# trehacklab_doorbell.net
KiCad netlist of a schematic drawn in EAGLE
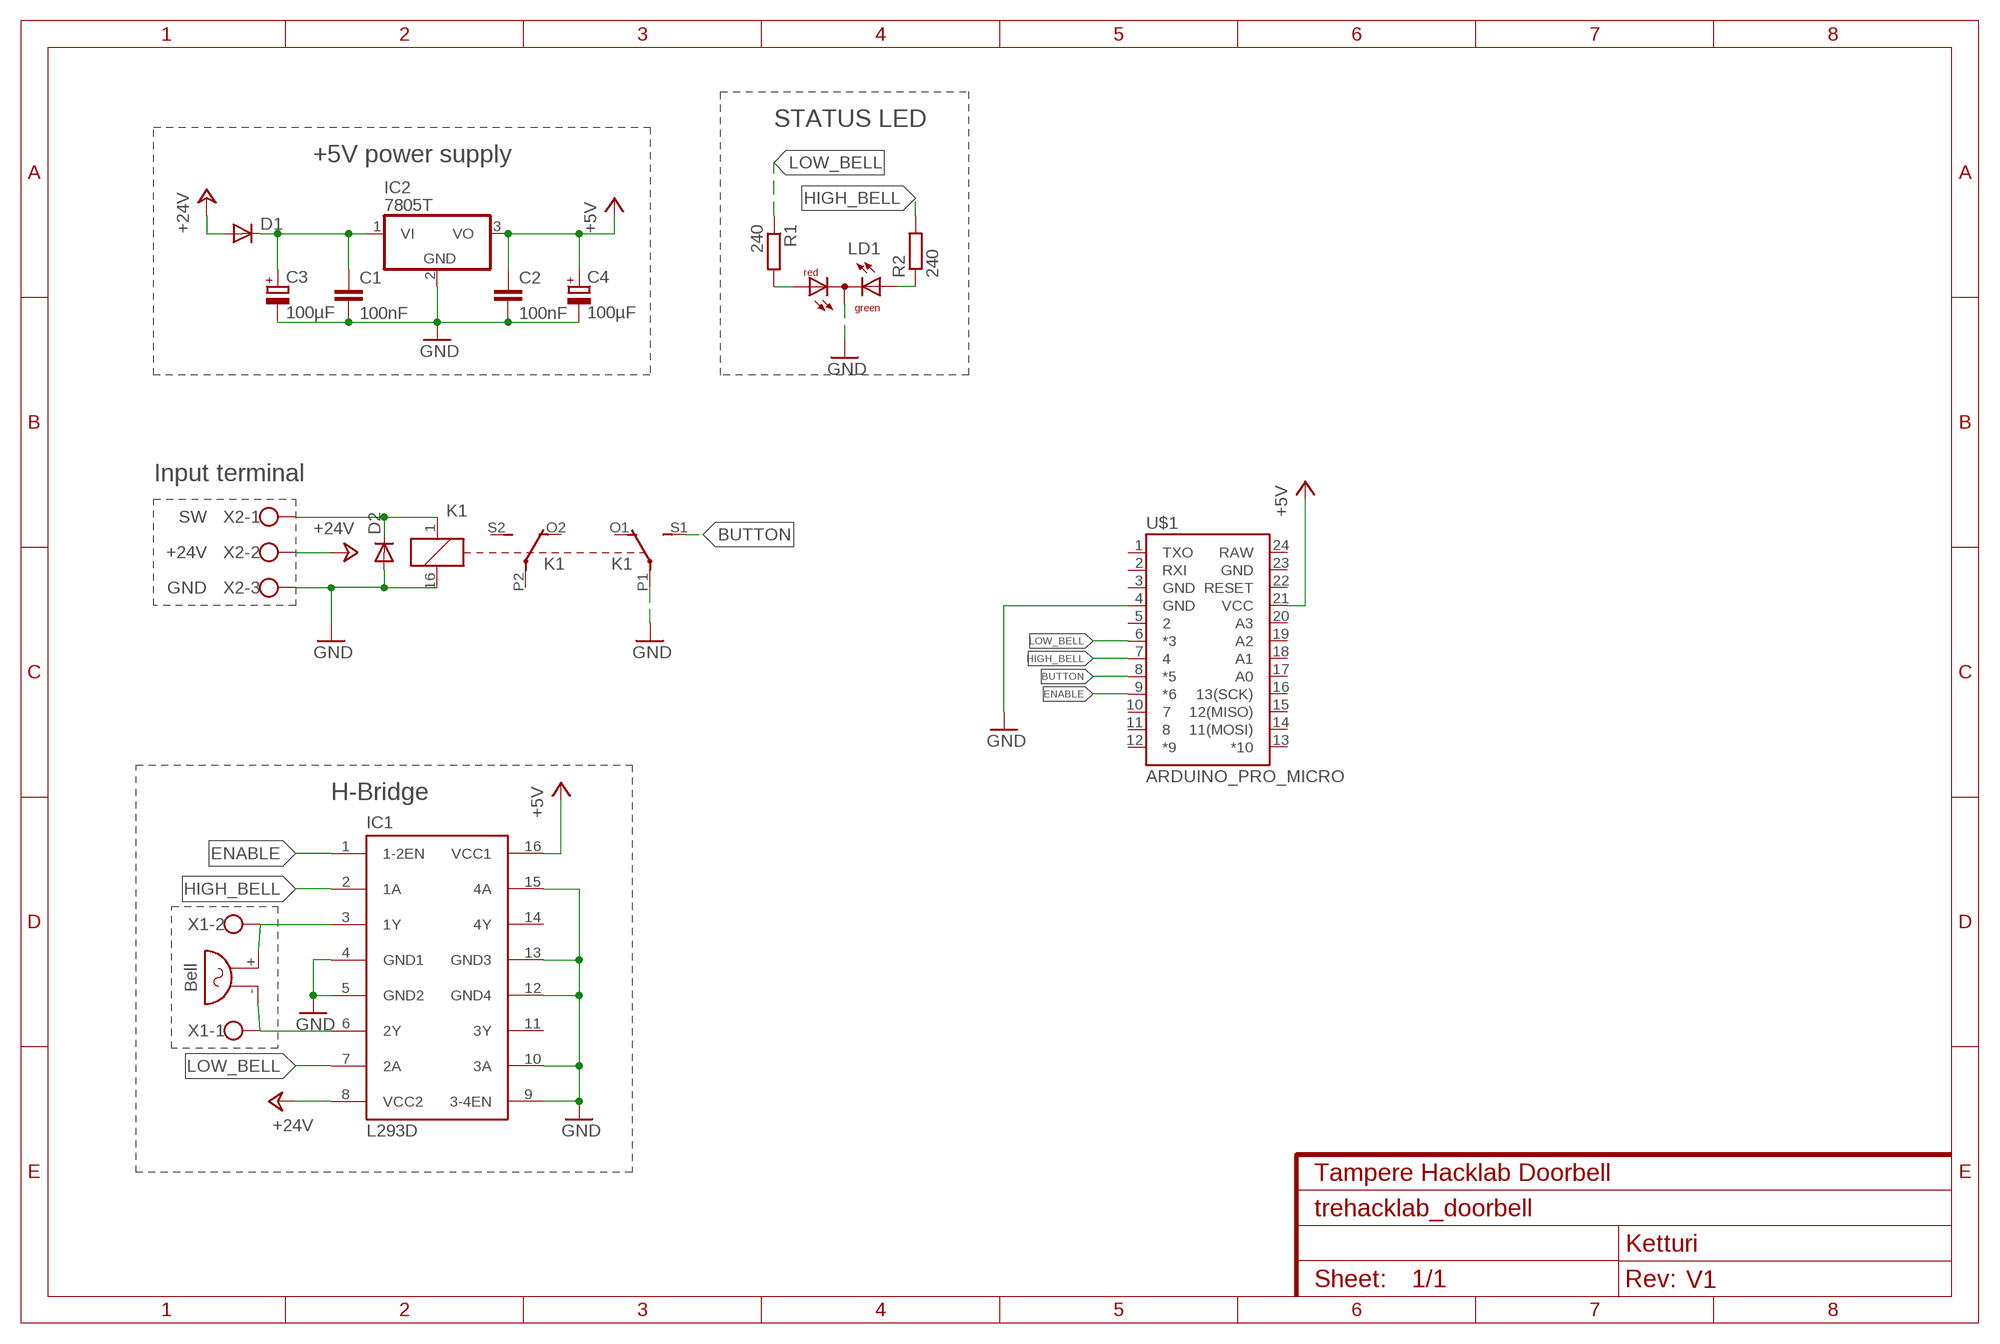
[diagram p0: schematic, sheet 1]

(export (version "E")
  (design (tool "Eeschema 10.0.6"))
  (components
    (comp (ref "C1")
      (value "100nF")
      (footprint "eagle-import:C025-024X044")
      (libsource (lib "eagle-import") (part "C-EU025-024X044"))
    )
    (comp (ref "C2")
      (value "100nF")
      (footprint "eagle-import:C025-024X044")
      (libsource (lib "eagle-import") (part "C-EU025-024X044"))
    )
    (comp (ref "C3")
      (value "100µF")
      (footprint "eagle-import:E3,5-8")
      (libsource (lib "eagle-import") (part "CPOL-EUE3.5-8"))
    )
    (comp (ref "C4")
      (value "100µF")
      (footprint "eagle-import:E3,5-8")
      (libsource (lib "eagle-import") (part "CPOL-EUE3.5-8"))
    )
    (comp (ref "D1")
      (value "1N5624")
      (footprint "eagle-import:DO201-15")
      (libsource (lib "eagle-import") (part "1N5624"))
    )
    (comp (ref "D2")
      (value "1N5624")
      (footprint "eagle-import:DO201-15")
      (libsource (lib "eagle-import") (part "1N5624"))
    )
    (comp (ref "IC1")
      (value "L293D")
      (footprint "eagle-import:DIL16")
      (libsource (lib "eagle-import") (part "L293D"))
    )
    (comp (ref "IC2")
      (value "7805T")
      (footprint "eagle-import:TO220H")
      (libsource (lib "eagle-import") (part "78T05"))
    )
    (comp (ref "K1")
      (value "351")
      (footprint "eagle-import:351")
      (libsource (lib "eagle-import") (part "351"))
    )
    (comp (ref "LD1")
      (value "DUOLED-RG-C")
      (footprint "eagle-import:DUOLED-C-5MM")
      (libsource (lib "eagle-import") (part "DUOLED-RG-C"))
    )
    (comp (ref "R1")
      (value "240")
      (footprint "eagle-import:0204V")
      (libsource (lib "eagle-import") (part "R-EU_0204/2V"))
    )
    (comp (ref "R2")
      (value "240")
      (footprint "eagle-import:0204V")
      (libsource (lib "eagle-import") (part "R-EU_0204/2V"))
    )
    (comp (ref "SG1")
      (value "Bell")
      (footprint "eagle-import:F_QMX")
      (libsource (lib "eagle-import") (part "F/QMX"))
    )
    (comp (ref "U$1")
      (value "ARDUINO_PRO_MICRO")
      (footprint "eagle-import:ARDUINO_PRO_MICRO")
      (libsource (lib "eagle-import") (part "ARDUINO_PRO_MICRO"))
    )
    (comp (ref "X1")
      (value "W239-302")
      (footprint "eagle-import:W239-302")
      (libsource (lib "eagle-import") (part "W239-302"))
    )
    (comp (ref "X2")
      (value "W239-103")
      (footprint "eagle-import:W239-103")
      (fields (field (name "MPN") "239-103"))
      (libsource (lib "eagle-import") (part "W239-103"))
    )
  )
  (nets
    (net (code "1") (name "+5V") (class "Default")
      (node (ref "C2") (pin "1") (pinfunction "1_1") (pintype "passive"))
      (node (ref "C4") (pin "+") (pinfunction "+_+") (pintype "passive"))
      (node (ref "IC1") (pin "16") (pinfunction "VCC1_16") (pintype "power_in"))
      (node (ref "IC2") (pin "3") (pinfunction "VO_3") (pintype "passive"))
      (node (ref "U$1") (pin "21") (pinfunction "VCC_21") (pintype "bidirectional"))
    )
    (net (code "2") (name "+24V") (class "Default")
      (node (ref "D1") (pin "A") (pinfunction "A_A") (pintype "passive"))
      (node (ref "IC1") (pin "8") (pinfunction "VCC2_8") (pintype "power_in"))
      (node (ref "X2") (pin "2") (pinfunction "KL_2") (pintype "passive"))
    )
    (net (code "3") (name "BUTTON") (class "Default")
      (node (ref "K1") (pin "S1") (pinfunction "S_S1") (pintype "passive"))
      (node (ref "U$1") (pin "8") (pinfunction "*5_8") (pintype "bidirectional"))
    )
    (net (code "4") (name "ENABLE") (class "Default")
      (node (ref "IC1") (pin "1") (pinfunction "1-2EN_1") (pintype "input"))
      (node (ref "U$1") (pin "9") (pinfunction "*6_9") (pintype "bidirectional"))
    )
    (net (code "5") (name "GND") (class "Default")
      (node (ref "C1") (pin "2") (pinfunction "2_2") (pintype "passive"))
      (node (ref "C2") (pin "2") (pinfunction "2_2") (pintype "passive"))
      (node (ref "C3") (pin "-") (pinfunction "-_-") (pintype "passive"))
      (node (ref "C4") (pin "-") (pinfunction "-_-") (pintype "passive"))
      (node (ref "D2") (pin "A") (pinfunction "A_A") (pintype "passive"))
      (node (ref "IC1") (pin "10") (pinfunction "3A_10") (pintype "input"))
      (node (ref "IC1") (pin "12") (pinfunction "GND4_12") (pintype "power_in"))
      (node (ref "IC1") (pin "13") (pinfunction "GND3_13") (pintype "power_in"))
      (node (ref "IC1") (pin "15") (pinfunction "4A_15") (pintype "input"))
      (node (ref "IC1") (pin "4") (pinfunction "GND1_4") (pintype "power_in"))
      (node (ref "IC1") (pin "5") (pinfunction "GND2_5") (pintype "power_in"))
      (node (ref "IC1") (pin "9") (pinfunction "3-4EN_9") (pintype "input"))
      (node (ref "IC2") (pin "2") (pinfunction "GND_2") (pintype "passive"))
      (node (ref "K1") (pin "16") (pinfunction "2_16") (pintype "passive"))
      (node (ref "K1") (pin "P1") (pinfunction "P_P1") (pintype "passive"))
      (node (ref "LD1") (pin "C") (pinfunction "C_C") (pintype "passive"))
      (node (ref "U$1") (pin "4") (pinfunction "GND_4") (pintype "bidirectional"))
      (node (ref "X2") (pin "3") (pinfunction "KL_3") (pintype "passive"))
    )
    (net (code "6") (name "HIGH_BELL") (class "Default")
      (node (ref "IC1") (pin "2") (pinfunction "1A_2") (pintype "input"))
      (node (ref "R2") (pin "2") (pinfunction "2_2") (pintype "passive"))
      (node (ref "U$1") (pin "7") (pinfunction "4_7") (pintype "bidirectional"))
    )
    (net (code "7") (name "LOW_BELL") (class "Default")
      (node (ref "IC1") (pin "7") (pinfunction "2A_7") (pintype "input"))
      (node (ref "R1") (pin "1") (pinfunction "1_1") (pintype "passive"))
      (node (ref "U$1") (pin "6") (pinfunction "*3_6") (pintype "bidirectional"))
    )
    (net (code "8") (name "Net-(IC1-1Y)") (class "Default")
      (node (ref "IC1") (pin "3") (pinfunction "1Y_3") (pintype "output"))
      (node (ref "SG1") (pin "+") (pinfunction "2_+") (pintype "passive"))
      (node (ref "X1") (pin "2") (pinfunction "KL_2") (pintype "passive"))
    )
    (net (code "9") (name "Net-(IC1-2Y)") (class "Default")
      (node (ref "IC1") (pin "6") (pinfunction "2Y_6") (pintype "output"))
      (node (ref "SG1") (pin "-") (pinfunction "1_-") (pintype "passive"))
      (node (ref "X1") (pin "1") (pinfunction "KL_1") (pintype "passive"))
    )
    (net (code "10") (name "Net-(IC2-VI)") (class "Default")
      (node (ref "C1") (pin "1") (pinfunction "1_1") (pintype "passive"))
      (node (ref "C3") (pin "+") (pinfunction "+_+") (pintype "passive"))
      (node (ref "D1") (pin "C") (pinfunction "C_C") (pintype "passive"))
      (node (ref "IC2") (pin "1") (pinfunction "VI_1") (pintype "input"))
    )
    (net (code "11") (name "Net-(LD1-AG)") (class "Default")
      (node (ref "LD1") (pin "AX") (pinfunction "AG_AX") (pintype "passive"))
      (node (ref "R2") (pin "1") (pinfunction "1_1") (pintype "passive"))
    )
    (net (code "12") (name "Net-(LD1-PadAR)") (class "Default")
      (node (ref "LD1") (pin "AR") (pinfunction "AR_AR") (pintype "passive"))
      (node (ref "R1") (pin "2") (pinfunction "2_2") (pintype "passive"))
    )
    (net (code "13") (name "Net-(X2A-KL)") (class "Default")
      (node (ref "D2") (pin "C") (pinfunction "C_C") (pintype "passive"))
      (node (ref "K1") (pin "1") (pinfunction "1_1") (pintype "passive"))
      (node (ref "X2") (pin "1") (pinfunction "KL_1") (pintype "passive"))
    )
    (net (code "14") (name "unconnected-(IC1-3Y-Pad11)") (class "Default")
      (node (ref "IC1") (pin "11") (pinfunction "3Y_11") (pintype "output"))
    )
    (net (code "15") (name "unconnected-(IC1-4Y-Pad14)") (class "Default")
      (node (ref "IC1") (pin "14") (pinfunction "4Y_14") (pintype "output"))
    )
    (net (code "16") (name "unconnected-(K1B-O-PadO1)") (class "Default")
      (node (ref "K1") (pin "O1") (pinfunction "O_O1") (pintype "passive"))
    )
    (net (code "17") (name "unconnected-(K1C-O-PadO2)") (class "Default")
      (node (ref "K1") (pin "O2") (pinfunction "O_O2") (pintype "passive"))
    )
    (net (code "18") (name "unconnected-(K1C-P-PadP2)") (class "Default")
      (node (ref "K1") (pin "P2") (pinfunction "P_P2") (pintype "passive"))
    )
    (net (code "19") (name "unconnected-(K1C-S-PadS2)") (class "Default")
      (node (ref "K1") (pin "S2") (pinfunction "S_S2") (pintype "passive"))
    )
    (net (code "20") (name "unconnected-(U$1-*9-Pad12)") (class "Default")
      (node (ref "U$1") (pin "12") (pinfunction "*9_12") (pintype "bidirectional"))
    )
    (net (code "21") (name "unconnected-(U$1-*10-Pad13)") (class "Default")
      (node (ref "U$1") (pin "13") (pinfunction "*10_13") (pintype "bidirectional"))
    )
    (net (code "22") (name "unconnected-(U$1-2-Pad5)") (class "Default")
      (node (ref "U$1") (pin "5") (pinfunction "2_5") (pintype "bidirectional"))
    )
    (net (code "23") (name "unconnected-(U$1-7-Pad10)") (class "Default")
      (node (ref "U$1") (pin "10") (pinfunction "7_10") (pintype "bidirectional"))
    )
    (net (code "24") (name "unconnected-(U$1-8-Pad11)") (class "Default")
      (node (ref "U$1") (pin "11") (pinfunction "8_11") (pintype "bidirectional"))
    )
    (net (code "25") (name "unconnected-(U$1-11(MOSI)-Pad14)") (class "Default")
      (node (ref "U$1") (pin "14") (pinfunction "11(MOSI)_14") (pintype "bidirectional"))
    )
    (net (code "26") (name "unconnected-(U$1-12(MISO)-Pad15)") (class "Default")
      (node (ref "U$1") (pin "15") (pinfunction "12(MISO)_15") (pintype "bidirectional"))
    )
    (net (code "27") (name "unconnected-(U$1-13(SCK)-Pad16)") (class "Default")
      (node (ref "U$1") (pin "16") (pinfunction "13(SCK)_16") (pintype "bidirectional"))
    )
    (net (code "28") (name "unconnected-(U$1-A0-Pad17)") (class "Default")
      (node (ref "U$1") (pin "17") (pinfunction "A0_17") (pintype "bidirectional"))
    )
    (net (code "29") (name "unconnected-(U$1-A1-Pad18)") (class "Default")
      (node (ref "U$1") (pin "18") (pinfunction "A1_18") (pintype "bidirectional"))
    )
    (net (code "30") (name "unconnected-(U$1-A2-Pad19)") (class "Default")
      (node (ref "U$1") (pin "19") (pinfunction "A2_19") (pintype "bidirectional"))
    )
    (net (code "31") (name "unconnected-(U$1-A3-Pad20)") (class "Default")
      (node (ref "U$1") (pin "20") (pinfunction "A3_20") (pintype "bidirectional"))
    )
    (net (code "32") (name "unconnected-(U$1-GND-Pad3)") (class "Default")
      (node (ref "U$1") (pin "3") (pinfunction "GND_3") (pintype "bidirectional"))
    )
    (net (code "33") (name "unconnected-(U$1-GND-Pad23)") (class "Default")
      (node (ref "U$1") (pin "23") (pinfunction "GND_23") (pintype "bidirectional"))
    )
    (net (code "34") (name "unconnected-(U$1-RAW-Pad24)") (class "Default")
      (node (ref "U$1") (pin "24") (pinfunction "RAW_24") (pintype "bidirectional"))
    )
    (net (code "35") (name "unconnected-(U$1-RESET-Pad22)") (class "Default")
      (node (ref "U$1") (pin "22") (pinfunction "RESET_22") (pintype "bidirectional"))
    )
    (net (code "36") (name "unconnected-(U$1-RXI-Pad2)") (class "Default")
      (node (ref "U$1") (pin "2") (pinfunction "RXI_2") (pintype "bidirectional"))
    )
    (net (code "37") (name "unconnected-(U$1-TXO-Pad1)") (class "Default")
      (node (ref "U$1") (pin "1") (pinfunction "TXO_1") (pintype "bidirectional"))
    )
  )
)
